# SunnyBuddy.net
KiCad netlist of a schematic drawn in EAGLE
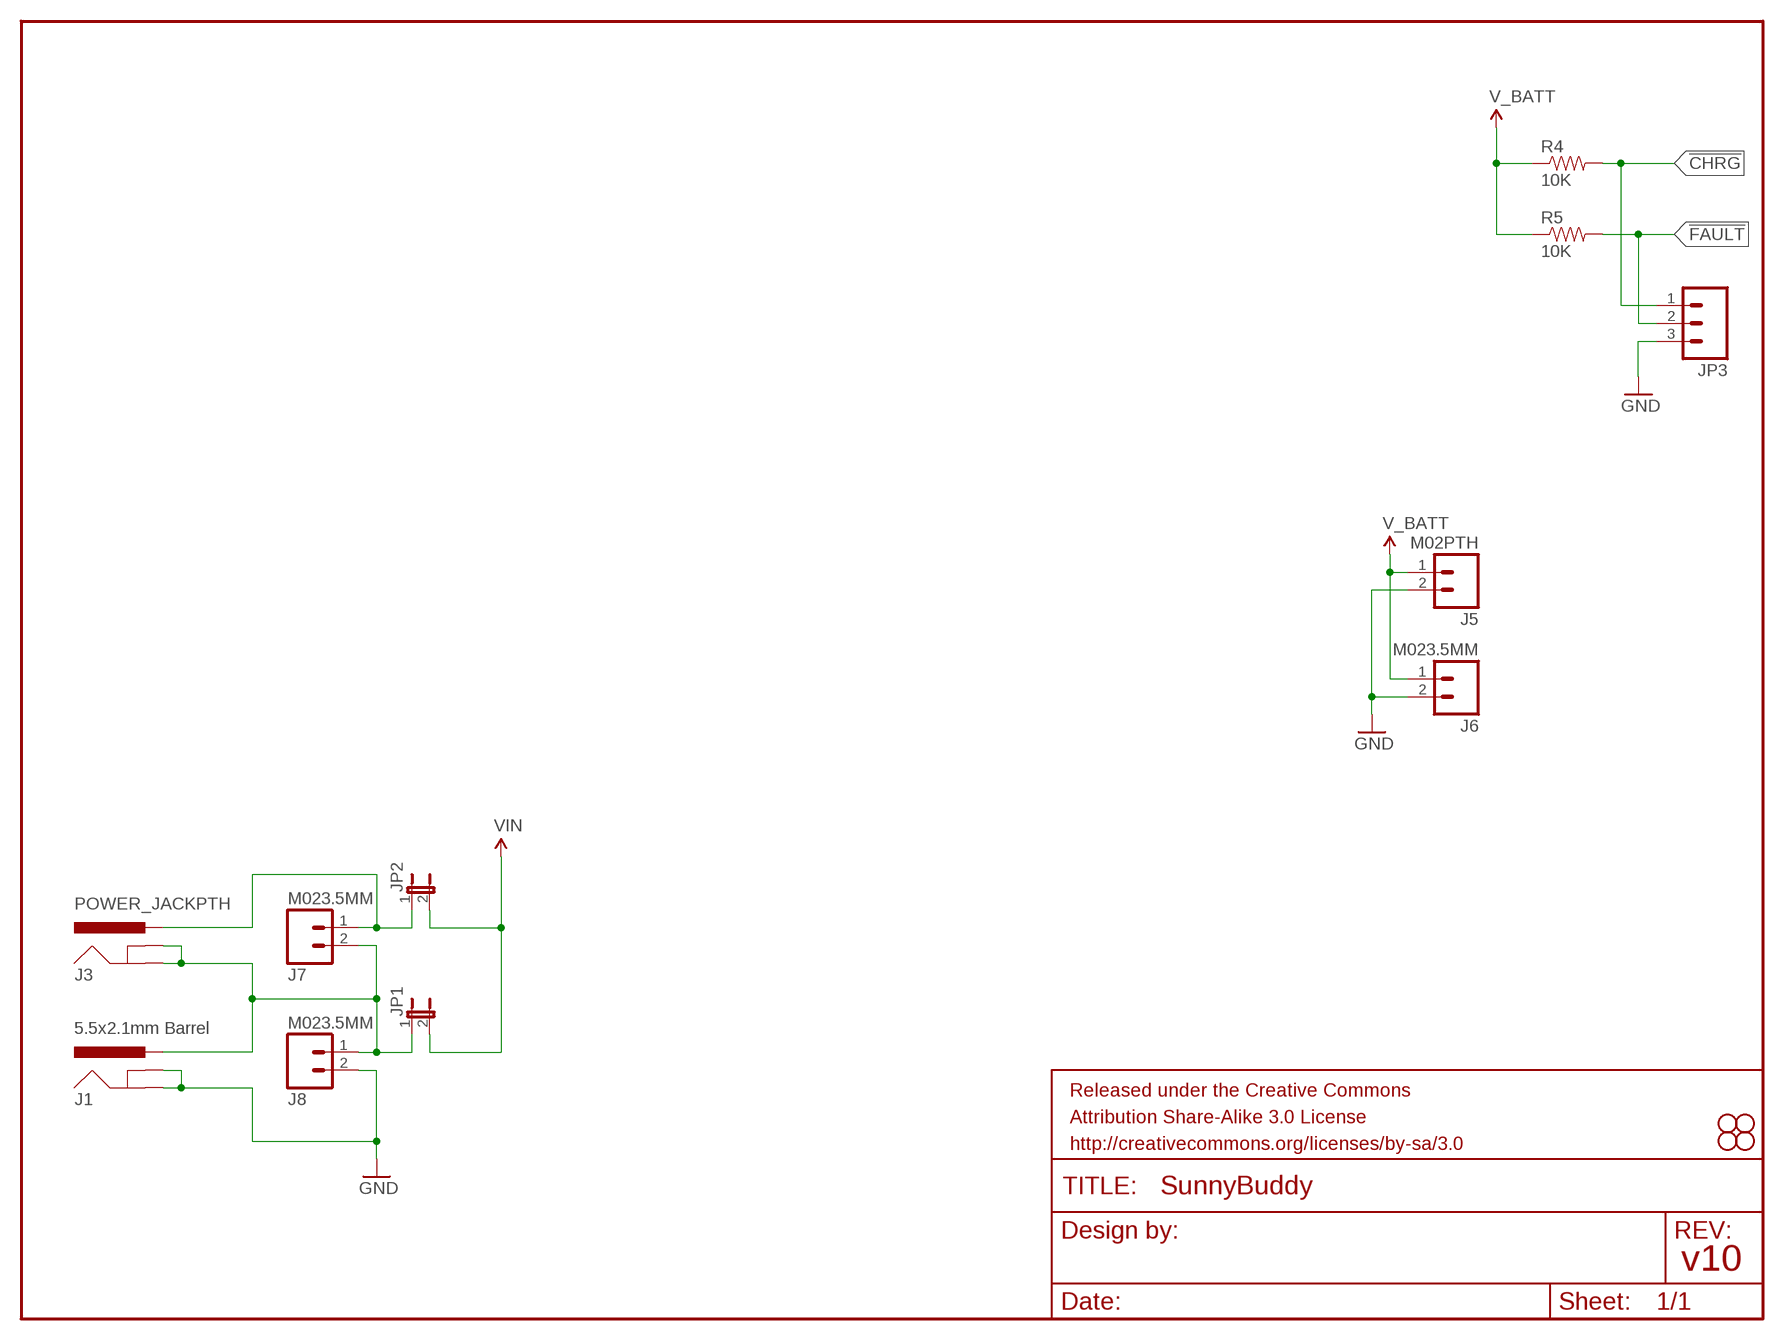
[diagram p0: schematic, sheet 1]

(export (version "E")
  (design (tool "Eeschema 10.0.6"))
  (components
    (comp (ref "FRAME1")
      (value "FRAME-LETTER")
      (footprint "eagle-import:CREATIVE_COMMONS")
      (libsource (lib "eagle-import") (part "FRAME-LETTER"))
    )
    (comp (ref "J1")
      (value "5.5x2.1mm Barrel")
      (footprint "eagle-import:POWER_JACK_SMD")
      (libsource (lib "eagle-import") (part "POWER_JACKSMD"))
    )
    (comp (ref "J3")
      (value "POWER_JACKPTH")
      (footprint "eagle-import:POWER_JACK_PTH")
      (libsource (lib "eagle-import") (part "POWER_JACKPTH"))
    )
    (comp (ref "J5")
      (value "M02PTH")
      (footprint "eagle-import:1X02")
      (libsource (lib "eagle-import") (part "M02PTH"))
    )
    (comp (ref "J6")
      (value "M023.5MM")
      (footprint "eagle-import:SCREWTERMINAL-3.5MM-2")
      (libsource (lib "eagle-import") (part "M023.5MM"))
    )
    (comp (ref "J7")
      (value "M023.5MM")
      (footprint "eagle-import:SCREWTERMINAL-3.5MM-2")
      (libsource (lib "eagle-import") (part "M023.5MM"))
    )
    (comp (ref "J8")
      (value "M023.5MM")
      (footprint "eagle-import:SCREWTERMINAL-3.5MM-2")
      (libsource (lib "eagle-import") (part "M023.5MM"))
    )
    (comp (ref "JP1")
      (value "JUMPER-2SMD-NC")
      (footprint "eagle-import:SJ_2S")
      (libsource (lib "eagle-import") (part "JUMPER-2SMD-NC"))
    )
    (comp (ref "JP2")
      (value "JUMPER-2SMD-NO")
      (footprint "eagle-import:SJ_2S-NO")
      (libsource (lib "eagle-import") (part "JUMPER-2SMD-NO"))
    )
    (comp (ref "JP3")
      (value "M03PTH")
      (footprint "eagle-import:1X03")
      (libsource (lib "eagle-import") (part "M03PTH"))
    )
    (comp (ref "R4")
      (value "10K")
      (footprint "eagle-import:0603-RES")
      (libsource (lib "eagle-import") (part "10KOHM1/10W1%(0603)0603"))
    )
    (comp (ref "R5")
      (value "10K")
      (footprint "eagle-import:0603-RES")
      (libsource (lib "eagle-import") (part "10KOHM1/10W1%(0603)0603"))
    )
    (comp (ref "STANDOFF1")
      (value "STAND-OFF")
      (footprint "eagle-import:STAND-OFF")
      (libsource (lib "eagle-import") (part "STAND-OFF"))
    )
    (comp (ref "STANDOFF2")
      (value "STAND-OFF")
      (footprint "eagle-import:STAND-OFF")
      (libsource (lib "eagle-import") (part "STAND-OFF"))
    )
    (comp (ref "STANDOFF3")
      (value "STAND-OFF")
      (footprint "eagle-import:STAND-OFF")
      (libsource (lib "eagle-import") (part "STAND-OFF"))
    )
    (comp (ref "STANDOFF4")
      (value "STAND-OFF")
      (footprint "eagle-import:STAND-OFF")
      (libsource (lib "eagle-import") (part "STAND-OFF"))
    )
  )
  (nets
    (net (code "1") (name "/~{CHRG}") (class "Default")
      (node (ref "JP3") (pin "1") (pinfunction "1_1") (pintype "passive"))
      (node (ref "R4") (pin "2") (pinfunction "2_2") (pintype "passive"))
    )
    (net (code "2") (name "/~{FAULT}") (class "Default")
      (node (ref "JP3") (pin "2") (pinfunction "2_2") (pintype "passive"))
      (node (ref "R5") (pin "2") (pinfunction "2_2") (pintype "passive"))
    )
    (net (code "3") (name "GND") (class "Default")
      (node (ref "J1") (pin "GND") (pinfunction "GNDBREAK_GND") (pintype "bidirectional"))
      (node (ref "J1") (pin "P$4") (pinfunction "GND_P$4") (pintype "bidirectional"))
      (node (ref "J5") (pin "2") (pinfunction "2_2") (pintype "passive"))
      (node (ref "J6") (pin "2") (pinfunction "2_2") (pintype "passive"))
      (node (ref "J8") (pin "2") (pinfunction "2_2") (pintype "passive"))
      (node (ref "JP3") (pin "3") (pinfunction "3_3") (pintype "passive"))
    )
    (net (code "4") (name "Net-(J1-PWR)") (class "Default")
      (node (ref "J1") (pin "VIN0") (pinfunction "PWR_VIN0") (pintype "bidirectional"))
      (node (ref "J3") (pin "GND") (pinfunction "GND_GND") (pintype "bidirectional"))
      (node (ref "J3") (pin "GNDBREAK") (pinfunction "GNDBREAK_GNDBREAK") (pintype "bidirectional"))
      (node (ref "J7") (pin "2") (pinfunction "2_2") (pintype "passive"))
      (node (ref "J8") (pin "1") (pinfunction "1_1") (pintype "passive"))
      (node (ref "JP1") (pin "1") (pinfunction "1_1") (pintype "passive"))
    )
    (net (code "5") (name "Net-(J3-PadPWR)") (class "Default")
      (node (ref "J3") (pin "PWR") (pinfunction "PWR_PWR") (pintype "bidirectional"))
      (node (ref "J7") (pin "1") (pinfunction "1_1") (pintype "passive"))
      (node (ref "JP2") (pin "1") (pinfunction "1_1") (pintype "passive"))
    )
    (net (code "6") (name "VIN") (class "Default")
      (node (ref "JP1") (pin "2") (pinfunction "2_2") (pintype "passive"))
      (node (ref "JP2") (pin "2") (pinfunction "2_2") (pintype "passive"))
    )
    (net (code "7") (name "V_BATT") (class "Default")
      (node (ref "J5") (pin "1") (pinfunction "1_1") (pintype "passive"))
      (node (ref "J6") (pin "1") (pinfunction "1_1") (pintype "passive"))
      (node (ref "R4") (pin "1") (pinfunction "1_1") (pintype "passive"))
      (node (ref "R5") (pin "1") (pinfunction "1_1") (pintype "passive"))
    )
  )
)
